# Signal_Conditioner.net
KiCad netlist of a schematic drawn in Altium Designer
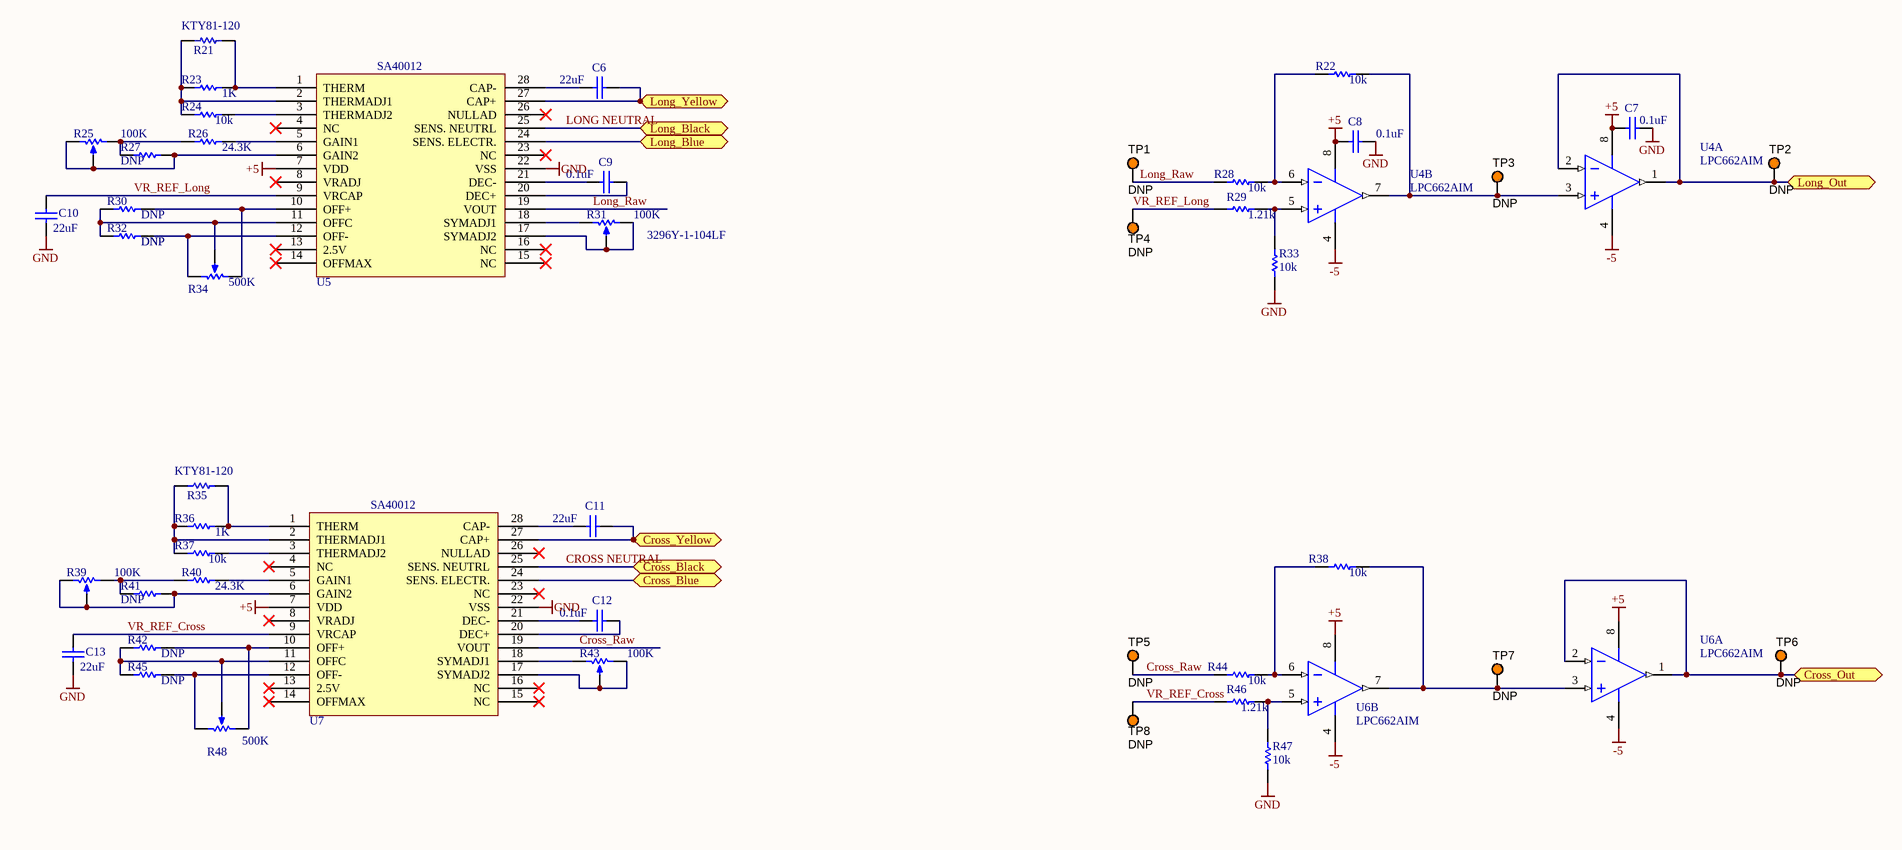
[diagram p0: Signal_Conditioner.SchDoc]

(export (version "E")
  (design (tool "Eeschema 10.0.6"))
  (components
    (comp (ref "C6")
      (value "22uF")
      (footprint "CAPC0805(2012)145_N")
      (description "CAP CER 22UF 16V X5R 0805")
      (fields
        (field (name "MANUFACTURER") "Murata Electronics North America")
        (field (name "MANUFACTURER PART NUMBER") "GRM219R61C226ME15L")
      )
      (libsource (lib "Altium Content Vault") (part "CMP-1036-04795-1"))
    )
    (comp (ref "C7")
      (value "0.1uF")
      (footprint "CAPC0402(1005)60_L")
      (description "CAP CER 0.1UF 10V X7R 0402")
      (fields
        (field (name "MANUFACTURER") "Murata Electronics North America")
        (field (name "MANUFACTURER PART NUMBER") "GRM155R71A104KA01D")
      )
      (libsource (lib "Altium Content Vault") (part "CMP-1034-00252-1"))
    )
    (comp (ref "C8")
      (value "0.1uF")
      (footprint "CAPC0402(1005)60_L")
      (description "CAP CER 0.1UF 10V X7R 0402")
      (fields
        (field (name "MANUFACTURER") "Murata Electronics North America")
        (field (name "MANUFACTURER PART NUMBER") "GRM155R71A104KA01D")
      )
      (libsource (lib "Altium Content Vault") (part "CMP-1034-00252-1"))
    )
    (comp (ref "C9")
      (value "0.1uF")
      (footprint "CAPC0402(1005)60_L")
      (description "CAP CER 0.1UF 10V X7R 0402")
      (libsource (lib "Altium Content Vault") (part "CMP-1034-00252-1"))
    )
    (comp (ref "C10")
      (value "22uF")
      (footprint "CAPC0805(2012)145_N")
      (description "CAP CER 22UF 16V X5R 0805")
      (fields
        (field (name "MANUFACTURER") "Murata Electronics North America")
        (field (name "MANUFACTURER PART NUMBER") "GRM219R61C226ME15L")
      )
      (libsource (lib "Altium Content Vault") (part "CMP-1036-04795-1"))
    )
    (comp (ref "C11")
      (value "22uF")
      (footprint "CAPC0805(2012)145_N")
      (description "CAP CER 22UF 16V X5R 0805")
      (fields
        (field (name "MANUFACTURER") "Murata Electronics North America")
        (field (name "MANUFACTURER PART NUMBER") "GRM219R61C226ME15L")
      )
      (libsource (lib "Altium Content Vault") (part "CMP-1036-04795-1"))
    )
    (comp (ref "C12")
      (value "0.1uF")
      (footprint "CAPC0402(1005)60_L")
      (description "CAP CER 0.1UF 10V X7R 0402")
      (libsource (lib "Altium Content Vault") (part "CMP-1034-00252-1"))
    )
    (comp (ref "C13")
      (value "22uF")
      (footprint "CAPC0805(2012)145_N")
      (description "CAP CER 22UF 16V X5R 0805")
      (fields
        (field (name "MANUFACTURER") "Murata Electronics North America")
        (field (name "MANUFACTURER PART NUMBER") "GRM219R61C226ME15L")
      )
      (libsource (lib "Altium Content Vault") (part "CMP-1036-04795-1"))
    )
    (comp (ref "R21")
      (value "KTY81-120")
      (footprint "KTY81-120")
      (description "THERMISTOR PTC 1K OHM PBCYT2")
      (fields
        (field (name "MANUFACTURER") "NXP USA Inc.")
        (field (name "MANUFACTURER PART NUMBER") "KTY81/120,112")
      )
      (libsource (lib "ZLS_Schematic_lib") (part "KTY81-120"))
    )
    (comp (ref "R22")
      (value "10k")
      (footprint "RESC0805(2012)_L")
      (description "RES SMD 10K OHM 1% 1/8W 0805")
      (fields
        (field (name "MANUFACTURER") "Vishay Dale")
        (field (name "MANUFACTURER PART NUMBER") "CRCW080510K0FKEA")
      )
      (libsource (lib "Altium Content Vault") (part "CMP-1013-00393-1"))
    )
    (comp (ref "R23")
      (value "1K")
      (footprint "RESC0805(2012)_L")
      (description "RES SMD 1K OHM 1% 1/8W 0805")
      (fields
        (field (name "MANUFACTURER") "Vishay Dale")
        (field (name "MANUFACTURER PART NUMBER") "CRCW08051K00FKEA")
      )
      (libsource (lib "Altium Content Vault") (part "CMP-1013-00393-1"))
    )
    (comp (ref "R24")
      (value "10k")
      (footprint "RESC0805(2012)_L")
      (description "RES SMD 10K OHM 1% 1/8W 0805")
      (fields
        (field (name "MANUFACTURER") "Vishay Dale")
        (field (name "MANUFACTURER PART NUMBER") "CRCW080510K0FKEA")
      )
      (libsource (lib "Altium Content Vault") (part "CMP-1013-00393-1"))
    )
    (comp (ref "R25")
      (value "100K")
      (footprint "Trimmer 2.54")
      (description "TRIMMER 5K OHM 0.25W PC PIN")
      (fields
        (field (name "MANUFACTURER") "Bourns Inc.")
        (field (name "MANUFACTURER PART NUMBER") "3296Y-1-104LF")
      )
      (libsource (lib "ZLS_Schematic_lib") (part "Trimmer"))
    )
    (comp (ref "R26")
      (value "24.3K")
      (footprint "RESC0805(2012)_L")
      (description "RES SMD 24.3K OHM 1% 1/8W 0805")
      (fields
        (field (name "MANUFACTURER") "Vishay Dale")
        (field (name "MANUFACTURER PART NUMBER") "CRCW080524K3FKEA")
      )
      (libsource (lib "Altium Content Vault") (part "CMP-1013-00393-1"))
    )
    (comp (ref "R27")
      (value "DNP")
      (footprint "RESC0805(2012)_L")
      (description "RES SMD 10K OHM 1% 1/8W 0805")
      (fields
        (field (name "MANUFACTURER") "Vishay Dale")
        (field (name "MANUFACTURER PART NUMBER") "CRCW080510K0FKEA")
      )
      (libsource (lib "Altium Content Vault") (part "CMP-1013-00393-1"))
    )
    (comp (ref "R28")
      (value "10k")
      (footprint "RESC0805(2012)_L")
      (description "RES SMD 10K OHM 1% 1/8W 0805")
      (fields
        (field (name "MANUFACTURER") "Vishay Dale")
        (field (name "MANUFACTURER PART NUMBER") "CRCW080510K0FKEA")
      )
      (libsource (lib "Altium Content Vault") (part "CMP-1013-00393-1"))
    )
    (comp (ref "R29")
      (value "1.21k")
      (footprint "RESC0805(2012)_L")
      (description "RES SMD 1.21K OHM 1% 1/8W 0805")
      (fields
        (field (name "MANUFACTURER") "Vishay Dale")
        (field (name "MANUFACTURER PART NUMBER") "CRCW08051K21FKEA")
      )
      (libsource (lib "Altium Content Vault") (part "CMP-1013-00393-1"))
    )
    (comp (ref "R30")
      (value "DNP")
      (footprint "RESC0805(2012)_L")
      (description "RES SMD 249K OHM 1% 1/8W 0805")
      (fields
        (field (name "MANUFACTURER") "Vishay Dale")
        (field (name "MANUFACTURER PART NUMBER") "CRCW0805249KFKECC")
      )
      (libsource (lib "Altium Content Vault") (part "CMP-1013-00393-1"))
    )
    (comp (ref "R31")
      (value "100K")
      (footprint "Trimmer 2.54")
      (description "TRIMMER 5K OHM 0.25W PC PIN")
      (fields
        (field (name "MANUFACTURER") "Bourns Inc.")
        (field (name "MANUFACTURER PART NUMBER") "3296Y-1-104LF")
      )
      (libsource (lib "ZLS_Schematic_lib") (part "Trimmer"))
    )
    (comp (ref "R32")
      (value "DNP")
      (footprint "RESC0805(2012)_L")
      (description "RES SMD 249K OHM 1% 1/8W 0805")
      (fields
        (field (name "MANUFACTURER") "Vishay Dale")
        (field (name "MANUFACTURER PART NUMBER") "CRCW0805249KFKECC")
      )
      (libsource (lib "Altium Content Vault") (part "CMP-1013-00393-1"))
    )
    (comp (ref "R33")
      (value "10k")
      (footprint "RESC0805(2012)_L")
      (description "RES SMD 10K OHM 1% 1/8W 0805")
      (fields
        (field (name "MANUFACTURER") "Vishay Dale")
        (field (name "MANUFACTURER PART NUMBER") "CRCW080510K0FKEA")
      )
      (libsource (lib "Altium Content Vault") (part "CMP-1013-00393-1"))
    )
    (comp (ref "R34")
      (value "500K")
      (footprint "Trimmer 2.54")
      (description "TRIMMER 500K OHM 0.5W PC PIN TOP")
      (fields
        (field (name "MANUFACTURER") "Bourns Inc.")
        (field (name "MANUFACTURER PART NUMBER") "3296Y-1-504LF")
      )
      (libsource (lib "ZLS_Schematic_lib") (part "Trimmer"))
    )
    (comp (ref "R35")
      (value "KTY81-120")
      (footprint "KTY81-120")
      (description "THERMISTOR PTC 1K OHM PBCYT2")
      (fields
        (field (name "MANUFACTURER") "NXP USA Inc.")
        (field (name "MANUFACTURER PART NUMBER") "KTY81/120,112")
      )
      (libsource (lib "ZLS_Schematic_lib") (part "KTY81-120"))
    )
    (comp (ref "R36")
      (value "1K")
      (footprint "RESC0805(2012)_L")
      (description "RES SMD 1K OHM 1% 1/8W 0805")
      (fields
        (field (name "MANUFACTURER") "Vishay Dale")
        (field (name "MANUFACTURER PART NUMBER") "CRCW08051K00FKEA")
      )
      (libsource (lib "Altium Content Vault") (part "CMP-1013-00393-1"))
    )
    (comp (ref "R37")
      (value "10k")
      (footprint "RESC0805(2012)_L")
      (description "RES SMD 10K OHM 1% 1/8W 0805")
      (fields
        (field (name "MANUFACTURER") "Vishay Dale")
        (field (name "MANUFACTURER PART NUMBER") "CRCW080510K0FKEA")
      )
      (libsource (lib "Altium Content Vault") (part "CMP-1013-00393-1"))
    )
    (comp (ref "R38")
      (value "10k")
      (footprint "RESC0805(2012)_L")
      (description "RES SMD 10K OHM 1% 1/8W 0805")
      (fields
        (field (name "MANUFACTURER") "Vishay Dale")
        (field (name "MANUFACTURER PART NUMBER") "CRCW080510K0FKEA")
      )
      (libsource (lib "Altium Content Vault") (part "CMP-1013-00393-1"))
    )
    (comp (ref "R39")
      (value "100K")
      (footprint "Trimmer 2.54")
      (description "TRIMMER 5K OHM 0.25W PC PIN")
      (fields
        (field (name "MANUFACTURER") "Bourns Inc.")
        (field (name "MANUFACTURER PART NUMBER") "3296Y-1-104LF")
      )
      (libsource (lib "ZLS_Schematic_lib") (part "Trimmer"))
    )
    (comp (ref "R40")
      (value "24.3K")
      (footprint "RESC0805(2012)_L")
      (description "RES SMD 24.3K OHM 1% 1/8W 0805")
      (fields
        (field (name "MANUFACTURER") "Vishay Dale")
        (field (name "MANUFACTURER PART NUMBER") "CRCW080524K3FKEA")
      )
      (libsource (lib "Altium Content Vault") (part "CMP-1013-00393-1"))
    )
    (comp (ref "R41")
      (value "DNP")
      (footprint "RESC0805(2012)_L")
      (description "RES SMD 10K OHM 1% 1/8W 0805")
      (fields
        (field (name "MANUFACTURER") "Vishay Dale")
        (field (name "MANUFACTURER PART NUMBER") "CRCW080510K0FKEA")
      )
      (libsource (lib "Altium Content Vault") (part "CMP-1013-00393-1"))
    )
    (comp (ref "R42")
      (value "DNP")
      (footprint "RESC0805(2012)_L")
      (description "RES SMD 249K OHM 1% 1/8W 0805")
      (fields
        (field (name "MANUFACTURER") "Vishay Dale")
        (field (name "MANUFACTURER PART NUMBER") "CRCW0805249KFKECC")
      )
      (libsource (lib "Altium Content Vault") (part "CMP-1013-00393-1"))
    )
    (comp (ref "R43")
      (value "100K")
      (footprint "Trimmer 2.54")
      (description "TRIMMER 5K OHM 0.25W PC PIN")
      (fields
        (field (name "MANUFACTURER") "Bourns Inc.")
        (field (name "MANUFACTURER PART NUMBER") "3296Y-1-104LF")
      )
      (libsource (lib "ZLS_Schematic_lib") (part "Trimmer"))
    )
    (comp (ref "R44")
      (value "10k")
      (footprint "RESC0805(2012)_L")
      (description "RES SMD 10K OHM 1% 1/8W 0805")
      (fields
        (field (name "MANUFACTURER") "Vishay Dale")
        (field (name "MANUFACTURER PART NUMBER") "CRCW080510K0FKEA")
      )
      (libsource (lib "Altium Content Vault") (part "CMP-1013-00393-1"))
    )
    (comp (ref "R45")
      (value "DNP")
      (footprint "RESC0805(2012)_L")
      (description "RES SMD 249K OHM 1% 1/8W 0805")
      (fields
        (field (name "MANUFACTURER") "Vishay Dale")
        (field (name "MANUFACTURER PART NUMBER") "CRCW0805249KFKECC")
      )
      (libsource (lib "Altium Content Vault") (part "CMP-1013-00393-1"))
    )
    (comp (ref "R46")
      (value "1.21k")
      (footprint "RESC0805(2012)_L")
      (description "RES SMD 1.21K OHM 1% 1/8W 0805")
      (fields
        (field (name "MANUFACTURER") "Vishay Dale")
        (field (name "MANUFACTURER PART NUMBER") "CRCW08051K21FKEA")
      )
      (libsource (lib "Altium Content Vault") (part "CMP-1013-00393-1"))
    )
    (comp (ref "R47")
      (value "10k")
      (footprint "RESC0805(2012)_L")
      (description "RES SMD 10K OHM 1% 1/8W 0805")
      (fields
        (field (name "MANUFACTURER") "Vishay Dale")
        (field (name "MANUFACTURER PART NUMBER") "CRCW080510K0FKEA")
      )
      (libsource (lib "Altium Content Vault") (part "CMP-1013-00393-1"))
    )
    (comp (ref "R48")
      (value "500K")
      (footprint "Trimmer 2.54")
      (description "TRIMMER 500K OHM 0.5W PC PIN TOP")
      (fields
        (field (name "MANUFACTURER") "Bourns Inc.")
        (field (name "MANUFACTURER PART NUMBER") "3296Y-1-504LF")
      )
      (libsource (lib "ZLS_Schematic_lib") (part "Trimmer"))
    )
    (comp (ref "TP1")
      (value "DNP")
      (footprint "KSTN-5003")
      (description "Test Point, Orange, 1-Pin THD, RoHS")
      (fields
        (field (name "MANUFACTURER") "Keystone Electronics")
        (field (name "MANUFACTURER PART NUMBER") "5003")
      )
      (libsource (lib "Altium Content Vault") (part "CMP-1672-00009-1"))
    )
    (comp (ref "TP2")
      (value "DNP")
      (footprint "KSTN-5003")
      (description "Test Point, Orange, 1-Pin THD, RoHS")
      (fields
        (field (name "MANUFACTURER") "Keystone Electronics")
        (field (name "MANUFACTURER PART NUMBER") "5003")
      )
      (libsource (lib "Altium Content Vault") (part "CMP-1672-00009-1"))
    )
    (comp (ref "TP3")
      (value "DNP")
      (footprint "KSTN-5003")
      (description "Test Point, Orange, 1-Pin THD, RoHS")
      (fields
        (field (name "MANUFACTURER") "Keystone Electronics")
        (field (name "MANUFACTURER PART NUMBER") "5003")
      )
      (libsource (lib "Altium Content Vault") (part "CMP-1672-00009-1"))
    )
    (comp (ref "TP4")
      (value "DNP")
      (footprint "KSTN-5003")
      (description "Test Point, Orange, 1-Pin THD, RoHS")
      (fields
        (field (name "MANUFACTURER") "Keystone Electronics")
        (field (name "MANUFACTURER PART NUMBER") "5003")
      )
      (libsource (lib "Altium Content Vault") (part "CMP-1672-00009-1"))
    )
    (comp (ref "TP5")
      (value "DNP")
      (footprint "KSTN-5003")
      (description "Test Point, Orange, 1-Pin THD, RoHS")
      (fields
        (field (name "MANUFACTURER") "Keystone Electronics")
        (field (name "MANUFACTURER PART NUMBER") "5003")
      )
      (libsource (lib "Altium Content Vault") (part "CMP-1672-00009-1"))
    )
    (comp (ref "TP6")
      (value "DNP")
      (footprint "KSTN-5003")
      (description "Test Point, Orange, 1-Pin THD, RoHS")
      (fields
        (field (name "MANUFACTURER") "Keystone Electronics")
        (field (name "MANUFACTURER PART NUMBER") "5003")
      )
      (libsource (lib "Altium Content Vault") (part "CMP-1672-00009-1"))
    )
    (comp (ref "TP7")
      (value "DNP")
      (footprint "KSTN-5003")
      (description "Test Point, Orange, 1-Pin THD, RoHS")
      (fields
        (field (name "MANUFACTURER") "Keystone Electronics")
        (field (name "MANUFACTURER PART NUMBER") "5003")
      )
      (libsource (lib "Altium Content Vault") (part "CMP-1672-00009-1"))
    )
    (comp (ref "TP8")
      (value "DNP")
      (footprint "KSTN-5003")
      (description "Test Point, Orange, 1-Pin THD, RoHS")
      (fields
        (field (name "MANUFACTURER") "Keystone Electronics")
        (field (name "MANUFACTURER PART NUMBER") "5003")
      )
      (libsource (lib "Altium Content Vault") (part "CMP-1672-00009-1"))
    )
    (comp (ref "U4")
      (value "LPC662AIM")
      (footprint "D0008A_M")
      (description "Low Power CMOS Dual Operational Amplifier, 8-pin Narrow SOIC")
      (fields (field (name "MANUFACTURER") "Texas Instruments"))
      (libsource (lib "Altium Content Vault") (part "AMP-OPA-LM6132-8"))
    )
    (comp (ref "U5")
      (value "SA40012")
      (footprint "SA40012")
      (description "Single Axix CMOS Signal Conditioning Module")
      (fields (field (name "MANUFACTURER") "Spectron") (field (name "MANUFACTURER PART NUMBER") "A40012"))
      (libsource (lib "ZLS_Schematic_lib") (part "SA40012"))
    )
    (comp (ref "U6")
      (value "LPC662AIM")
      (footprint "D0008A_M")
      (description "Low Power CMOS Dual Operational Amplifier, 8-pin Narrow SOIC")
      (fields (field (name "MANUFACTURER") "Texas Instruments"))
      (libsource (lib "Altium Content Vault") (part "CMP-0055-00867-3"))
    )
    (comp (ref "U7")
      (value "SA40012")
      (footprint "SA40012")
      (description "Single Axix CMOS Signal Conditioning Module")
      (fields (field (name "MANUFACTURER") "Spectron") (field (name "MANUFACTURER PART NUMBER") "A40012"))
      (libsource (lib "ZLS_Schematic_lib") (part "SA40012"))
    )
  )
  (nets
    (net (code "1") (name "+5") (class "Default")
      (node (ref "C7") (pin "1") (pinfunction "1_1") (pintype "passive"))
      (node (ref "C8") (pin "1") (pinfunction "1_1") (pintype "passive"))
      (node (ref "U4") (pin "8") (pinfunction "V+_8") (pintype "power_in"))
      (node (ref "U5") (pin "7") (pinfunction "VDD_7") (pintype "passive"))
      (node (ref "U6") (pin "8") (pinfunction "V+_8") (pintype "power_in"))
      (node (ref "U7") (pin "7") (pinfunction "VDD_7") (pintype "passive"))
    )
    (net (code "2") (name "-5") (class "Default")
      (node (ref "U4") (pin "4") (pinfunction "V-_4") (pintype "power_in"))
      (node (ref "U6") (pin "4") (pinfunction "V-_4") (pintype "power_in"))
    )
    (net (code "3") (name "/CROSS NEUTRAL") (class "Default")
      (node (ref "U7") (pin "25") (pinfunction "SENS._NEUTRL_25") (pintype "passive"))
    )
    (net (code "4") (name "/Cross_Blue") (class "Default")
      (node (ref "U7") (pin "24") (pinfunction "SENS._ELECTR._24") (pintype "passive"))
    )
    (net (code "5") (name "/Cross_Out") (class "Default")
      (node (ref "TP6") (pin "1") (pinfunction "1_1") (pintype "passive"))
      (node (ref "U6") (pin "1") (pinfunction "OUTA_1") (pintype "output"))
      (node (ref "U6") (pin "2") (pinfunction "INA-_2") (pintype "input"))
    )
    (net (code "6") (name "/Cross_Raw") (class "Default")
      (node (ref "R44") (pin "1") (pinfunction "1_1") (pintype "passive"))
      (node (ref "TP5") (pin "1") (pinfunction "1_1") (pintype "passive"))
      (node (ref "U7") (pin "19") (pinfunction "VOUT_19") (pintype "passive"))
    )
    (net (code "7") (name "/Cross_Yellow") (class "Default")
      (node (ref "C11") (pin "2") (pinfunction "2_2") (pintype "passive"))
      (node (ref "U7") (pin "27") (pinfunction "CAP+_27") (pintype "passive"))
    )
    (net (code "8") (name "/LONG NEUTRAL") (class "Default")
      (node (ref "U5") (pin "25") (pinfunction "SENS._NEUTRL_25") (pintype "passive"))
    )
    (net (code "9") (name "/Long_Blue") (class "Default")
      (node (ref "U5") (pin "24") (pinfunction "SENS._ELECTR._24") (pintype "passive"))
    )
    (net (code "10") (name "/Long_Out") (class "Default")
      (node (ref "TP2") (pin "1") (pinfunction "1_1") (pintype "passive"))
      (node (ref "U4") (pin "1") (pinfunction "OUTA_1") (pintype "output"))
      (node (ref "U4") (pin "2") (pinfunction "INA-_2") (pintype "input"))
    )
    (net (code "11") (name "/Long_Raw") (class "Default")
      (node (ref "R28") (pin "1") (pinfunction "1_1") (pintype "passive"))
      (node (ref "TP1") (pin "1") (pinfunction "1_1") (pintype "passive"))
      (node (ref "U5") (pin "19") (pinfunction "VOUT_19") (pintype "passive"))
    )
    (net (code "12") (name "/Long_Yellow") (class "Default")
      (node (ref "C6") (pin "2") (pinfunction "2_2") (pintype "passive"))
      (node (ref "U5") (pin "27") (pinfunction "CAP+_27") (pintype "passive"))
    )
    (net (code "13") (name "/VR_REF_Cross") (class "Default")
      (node (ref "C13") (pin "1") (pinfunction "1_1") (pintype "passive"))
      (node (ref "R46") (pin "2") (pinfunction "2_2") (pintype "passive"))
      (node (ref "TP8") (pin "1") (pinfunction "1_1") (pintype "passive"))
      (node (ref "U7") (pin "9") (pinfunction "VRCAP_9") (pintype "passive"))
    )
    (net (code "14") (name "/VR_REF_Long") (class "Default")
      (node (ref "C10") (pin "1") (pinfunction "1_1") (pintype "passive"))
      (node (ref "R29") (pin "2") (pinfunction "2_2") (pintype "passive"))
      (node (ref "TP4") (pin "1") (pinfunction "1_1") (pintype "passive"))
      (node (ref "U5") (pin "9") (pinfunction "VRCAP_9") (pintype "passive"))
    )
    (net (code "15") (name "GND") (class "Default")
      (node (ref "C10") (pin "2") (pinfunction "2_2") (pintype "passive"))
      (node (ref "C13") (pin "2") (pinfunction "2_2") (pintype "passive"))
      (node (ref "C7") (pin "2") (pinfunction "2_2") (pintype "passive"))
      (node (ref "C8") (pin "2") (pinfunction "2_2") (pintype "passive"))
      (node (ref "R33") (pin "1") (pinfunction "1_1") (pintype "passive"))
      (node (ref "R47") (pin "1") (pinfunction "1_1") (pintype "passive"))
      (node (ref "U5") (pin "22") (pinfunction "VSS_22") (pintype "passive"))
      (node (ref "U7") (pin "22") (pinfunction "VSS_22") (pintype "passive"))
    )
    (net (code "16") (name "Net-(R25-a)") (class "Default")
      (node (ref "R25") (pin "1") (pinfunction "a_1") (pintype "passive"))
      (node (ref "R25") (pin "2") (pinfunction "b_2") (pintype "passive"))
      (node (ref "R27") (pin "2") (pinfunction "2_2") (pintype "passive"))
      (node (ref "U5") (pin "6") (pinfunction "GAIN2_6") (pintype "passive"))
    )
    (net (code "17") (name "Net-(R25-c)") (class "Default")
      (node (ref "R25") (pin "3") (pinfunction "c_3") (pintype "passive"))
      (node (ref "R26") (pin "1") (pinfunction "1_1") (pintype "passive"))
      (node (ref "R27") (pin "1") (pinfunction "1_1") (pintype "passive"))
    )
    (net (code "18") (name "Net-(R31-a)") (class "Default")
      (node (ref "R31") (pin "1") (pinfunction "a_1") (pintype "passive"))
      (node (ref "U5") (pin "18") (pinfunction "SYMADJ1_18") (pintype "passive"))
    )
    (net (code "19") (name "Net-(R31-b)") (class "Default")
      (node (ref "R31") (pin "2") (pinfunction "b_2") (pintype "passive"))
      (node (ref "R31") (pin "3") (pinfunction "c_3") (pintype "passive"))
      (node (ref "U5") (pin "17") (pinfunction "SYMADJ2_17") (pintype "passive"))
    )
    (net (code "20") (name "Net-(R34-a)") (class "Default")
      (node (ref "R30") (pin "2") (pinfunction "2_2") (pintype "passive"))
      (node (ref "R34") (pin "1") (pinfunction "a_1") (pintype "passive"))
      (node (ref "U5") (pin "10") (pinfunction "OFF+_10") (pintype "passive"))
    )
    (net (code "21") (name "Net-(R34-b)") (class "Default")
      (node (ref "R30") (pin "1") (pinfunction "1_1") (pintype "passive"))
      (node (ref "R32") (pin "1") (pinfunction "1_1") (pintype "passive"))
      (node (ref "R34") (pin "2") (pinfunction "b_2") (pintype "passive"))
      (node (ref "U5") (pin "11") (pinfunction "OFFC_11") (pintype "passive"))
    )
    (net (code "22") (name "Net-(R34-c)") (class "Default")
      (node (ref "R32") (pin "2") (pinfunction "2_2") (pintype "passive"))
      (node (ref "R34") (pin "3") (pinfunction "c_3") (pintype "passive"))
      (node (ref "U5") (pin "12") (pinfunction "OFF-_12") (pintype "passive"))
    )
    (net (code "23") (name "Net-(R39-a)") (class "Default")
      (node (ref "R39") (pin "1") (pinfunction "a_1") (pintype "passive"))
      (node (ref "R39") (pin "2") (pinfunction "b_2") (pintype "passive"))
      (node (ref "R41") (pin "2") (pinfunction "2_2") (pintype "passive"))
      (node (ref "U7") (pin "6") (pinfunction "GAIN2_6") (pintype "passive"))
    )
    (net (code "24") (name "Net-(R39-c)") (class "Default")
      (node (ref "R39") (pin "3") (pinfunction "c_3") (pintype "passive"))
      (node (ref "R40") (pin "1") (pinfunction "1_1") (pintype "passive"))
      (node (ref "R41") (pin "1") (pinfunction "1_1") (pintype "passive"))
    )
    (net (code "25") (name "Net-(R43-a)") (class "Default")
      (node (ref "R43") (pin "1") (pinfunction "a_1") (pintype "passive"))
      (node (ref "U7") (pin "18") (pinfunction "SYMADJ1_18") (pintype "passive"))
    )
    (net (code "26") (name "Net-(R43-b)") (class "Default")
      (node (ref "R43") (pin "2") (pinfunction "b_2") (pintype "passive"))
      (node (ref "R43") (pin "3") (pinfunction "c_3") (pintype "passive"))
      (node (ref "U7") (pin "17") (pinfunction "SYMADJ2_17") (pintype "passive"))
    )
    (net (code "27") (name "Net-(R48-a)") (class "Default")
      (node (ref "R42") (pin "2") (pinfunction "2_2") (pintype "passive"))
      (node (ref "R48") (pin "1") (pinfunction "a_1") (pintype "passive"))
      (node (ref "U7") (pin "10") (pinfunction "OFF+_10") (pintype "passive"))
    )
    (net (code "28") (name "Net-(R48-b)") (class "Default")
      (node (ref "R42") (pin "1") (pinfunction "1_1") (pintype "passive"))
      (node (ref "R45") (pin "1") (pinfunction "1_1") (pintype "passive"))
      (node (ref "R48") (pin "2") (pinfunction "b_2") (pintype "passive"))
      (node (ref "U7") (pin "11") (pinfunction "OFFC_11") (pintype "passive"))
    )
    (net (code "29") (name "Net-(R48-c)") (class "Default")
      (node (ref "R45") (pin "2") (pinfunction "2_2") (pintype "passive"))
      (node (ref "R48") (pin "3") (pinfunction "c_3") (pintype "passive"))
      (node (ref "U7") (pin "12") (pinfunction "OFF-_12") (pintype "passive"))
    )
    (net (code "30") (name "Net-(U4A-INA+)") (class "Default")
      (node (ref "R22") (pin "2") (pinfunction "2_2") (pintype "passive"))
      (node (ref "TP3") (pin "1") (pinfunction "1_1") (pintype "passive"))
      (node (ref "U4") (pin "3") (pinfunction "INA+_3") (pintype "input"))
      (node (ref "U4") (pin "7") (pinfunction "OUTB_7") (pintype "output"))
    )
    (net (code "31") (name "Net-(U4B-INB+)") (class "Default")
      (node (ref "R29") (pin "1") (pinfunction "1_1") (pintype "passive"))
      (node (ref "R33") (pin "2") (pinfunction "2_2") (pintype "passive"))
      (node (ref "U4") (pin "5") (pinfunction "INB+_5") (pintype "input"))
    )
    (net (code "32") (name "Net-(U4B-INB-)") (class "Default")
      (node (ref "R22") (pin "1") (pinfunction "1_1") (pintype "passive"))
      (node (ref "R28") (pin "2") (pinfunction "2_2") (pintype "passive"))
      (node (ref "U4") (pin "6") (pinfunction "INB-_6") (pintype "input"))
    )
    (net (code "33") (name "Net-(U5-CAP-)") (class "Default")
      (node (ref "C6") (pin "1") (pinfunction "1_1") (pintype "passive"))
      (node (ref "U5") (pin "28") (pinfunction "CAP-_28") (pintype "passive"))
    )
    (net (code "34") (name "Net-(U5-DEC+)") (class "Default")
      (node (ref "C9") (pin "1") (pinfunction "1_1") (pintype "passive"))
      (node (ref "U5") (pin "20") (pinfunction "DEC+_20") (pintype "passive"))
    )
    (net (code "35") (name "Net-(U5-DEC-)") (class "Default")
      (node (ref "C9") (pin "2") (pinfunction "2_2") (pintype "passive"))
      (node (ref "U5") (pin "21") (pinfunction "DEC-_21") (pintype "passive"))
    )
    (net (code "36") (name "Net-(U5-GAIN1)") (class "Default")
      (node (ref "R26") (pin "2") (pinfunction "2_2") (pintype "passive"))
      (node (ref "U5") (pin "5") (pinfunction "GAIN1_5") (pintype "passive"))
    )
    (net (code "37") (name "Net-(U5-THERM)") (class "Default")
      (node (ref "R21") (pin "2") (pinfunction "2_2") (pintype "passive"))
      (node (ref "R23") (pin "2") (pinfunction "2_2") (pintype "passive"))
      (node (ref "U5") (pin "1") (pinfunction "THERM_1") (pintype "passive"))
    )
    (net (code "38") (name "Net-(U5-THERMADJ1)") (class "Default")
      (node (ref "R21") (pin "1") (pinfunction "1_1") (pintype "passive"))
      (node (ref "R23") (pin "1") (pinfunction "1_1") (pintype "passive"))
      (node (ref "R24") (pin "1") (pinfunction "1_1") (pintype "passive"))
      (node (ref "U5") (pin "2") (pinfunction "THERMADJ1_2") (pintype "passive"))
    )
    (net (code "39") (name "Net-(U5-THERMADJ2)") (class "Default")
      (node (ref "R24") (pin "2") (pinfunction "2_2") (pintype "passive"))
      (node (ref "U5") (pin "3") (pinfunction "THERMADJ2_3") (pintype "passive"))
    )
    (net (code "40") (name "Net-(U6A-INA+)") (class "Default")
      (node (ref "R38") (pin "2") (pinfunction "2_2") (pintype "passive"))
      (node (ref "TP7") (pin "1") (pinfunction "1_1") (pintype "passive"))
      (node (ref "U6") (pin "3") (pinfunction "INA+_3") (pintype "input"))
      (node (ref "U6") (pin "7") (pinfunction "OUTB_7") (pintype "output"))
    )
    (net (code "41") (name "Net-(U6B-INB+)") (class "Default")
      (node (ref "R46") (pin "1") (pinfunction "1_1") (pintype "passive"))
      (node (ref "R47") (pin "2") (pinfunction "2_2") (pintype "passive"))
      (node (ref "U6") (pin "5") (pinfunction "INB+_5") (pintype "input"))
    )
    (net (code "42") (name "Net-(U6B-INB-)") (class "Default")
      (node (ref "R38") (pin "1") (pinfunction "1_1") (pintype "passive"))
      (node (ref "R44") (pin "2") (pinfunction "2_2") (pintype "passive"))
      (node (ref "U6") (pin "6") (pinfunction "INB-_6") (pintype "input"))
    )
    (net (code "43") (name "Net-(U7-CAP-)") (class "Default")
      (node (ref "C11") (pin "1") (pinfunction "1_1") (pintype "passive"))
      (node (ref "U7") (pin "28") (pinfunction "CAP-_28") (pintype "passive"))
    )
    (net (code "44") (name "Net-(U7-DEC+)") (class "Default")
      (node (ref "C12") (pin "1") (pinfunction "1_1") (pintype "passive"))
      (node (ref "U7") (pin "20") (pinfunction "DEC+_20") (pintype "passive"))
    )
    (net (code "45") (name "Net-(U7-DEC-)") (class "Default")
      (node (ref "C12") (pin "2") (pinfunction "2_2") (pintype "passive"))
      (node (ref "U7") (pin "21") (pinfunction "DEC-_21") (pintype "passive"))
    )
    (net (code "46") (name "Net-(U7-GAIN1)") (class "Default")
      (node (ref "R40") (pin "2") (pinfunction "2_2") (pintype "passive"))
      (node (ref "U7") (pin "5") (pinfunction "GAIN1_5") (pintype "passive"))
    )
    (net (code "47") (name "Net-(U7-THERM)") (class "Default")
      (node (ref "R35") (pin "2") (pinfunction "2_2") (pintype "passive"))
      (node (ref "R36") (pin "2") (pinfunction "2_2") (pintype "passive"))
      (node (ref "U7") (pin "1") (pinfunction "THERM_1") (pintype "passive"))
    )
    (net (code "48") (name "Net-(U7-THERMADJ1)") (class "Default")
      (node (ref "R35") (pin "1") (pinfunction "1_1") (pintype "passive"))
      (node (ref "R36") (pin "1") (pinfunction "1_1") (pintype "passive"))
      (node (ref "R37") (pin "1") (pinfunction "1_1") (pintype "passive"))
      (node (ref "U7") (pin "2") (pinfunction "THERMADJ1_2") (pintype "passive"))
    )
    (net (code "49") (name "Net-(U7-THERMADJ2)") (class "Default")
      (node (ref "R37") (pin "2") (pinfunction "2_2") (pintype "passive"))
      (node (ref "U7") (pin "3") (pinfunction "THERMADJ2_3") (pintype "passive"))
    )
    (net (code "50") (name "unconnected-(U5-2.5V-Pad13)") (class "Default")
      (node (ref "U5") (pin "13") (pinfunction "2.5V_13") (pintype "passive+no_connect"))
    )
    (net (code "51") (name "unconnected-(U5-NC-Pad4)") (class "Default")
      (node (ref "U5") (pin "4") (pinfunction "NC_4") (pintype "passive+no_connect"))
    )
    (net (code "52") (name "unconnected-(U5-NC-Pad15)") (class "Default")
      (node (ref "U5") (pin "15") (pinfunction "NC_15") (pintype "passive+no_connect"))
    )
    (net (code "53") (name "unconnected-(U5-NC-Pad16)") (class "Default")
      (node (ref "U5") (pin "16") (pinfunction "NC_16") (pintype "passive+no_connect"))
    )
    (net (code "54") (name "unconnected-(U5-NC-Pad23)") (class "Default")
      (node (ref "U5") (pin "23") (pinfunction "NC_23") (pintype "passive+no_connect"))
    )
    (net (code "55") (name "unconnected-(U5-NULLAD-Pad26)") (class "Default")
      (node (ref "U5") (pin "26") (pinfunction "NULLAD_26") (pintype "passive+no_connect"))
    )
    (net (code "56") (name "unconnected-(U5-OFFMAX-Pad14)") (class "Default")
      (node (ref "U5") (pin "14") (pinfunction "OFFMAX_14") (pintype "passive+no_connect"))
    )
    (net (code "57") (name "unconnected-(U5-VRADJ-Pad8)") (class "Default")
      (node (ref "U5") (pin "8") (pinfunction "VRADJ_8") (pintype "passive+no_connect"))
    )
    (net (code "58") (name "unconnected-(U7-2.5V-Pad13)") (class "Default")
      (node (ref "U7") (pin "13") (pinfunction "2.5V_13") (pintype "passive+no_connect"))
    )
    (net (code "59") (name "unconnected-(U7-NC-Pad4)") (class "Default")
      (node (ref "U7") (pin "4") (pinfunction "NC_4") (pintype "passive+no_connect"))
    )
    (net (code "60") (name "unconnected-(U7-NC-Pad15)") (class "Default")
      (node (ref "U7") (pin "15") (pinfunction "NC_15") (pintype "passive+no_connect"))
    )
    (net (code "61") (name "unconnected-(U7-NC-Pad16)") (class "Default")
      (node (ref "U7") (pin "16") (pinfunction "NC_16") (pintype "passive+no_connect"))
    )
    (net (code "62") (name "unconnected-(U7-NC-Pad23)") (class "Default")
      (node (ref "U7") (pin "23") (pinfunction "NC_23") (pintype "passive+no_connect"))
    )
    (net (code "63") (name "unconnected-(U7-NULLAD-Pad26)") (class "Default")
      (node (ref "U7") (pin "26") (pinfunction "NULLAD_26") (pintype "passive+no_connect"))
    )
    (net (code "64") (name "unconnected-(U7-OFFMAX-Pad14)") (class "Default")
      (node (ref "U7") (pin "14") (pinfunction "OFFMAX_14") (pintype "passive+no_connect"))
    )
    (net (code "65") (name "unconnected-(U7-VRADJ-Pad8)") (class "Default")
      (node (ref "U7") (pin "8") (pinfunction "VRADJ_8") (pintype "passive+no_connect"))
    )
  )
)
